# PowerWall_2020-05-24_01-53-03.net
KiCad netlist of a schematic drawn in EasyEDA
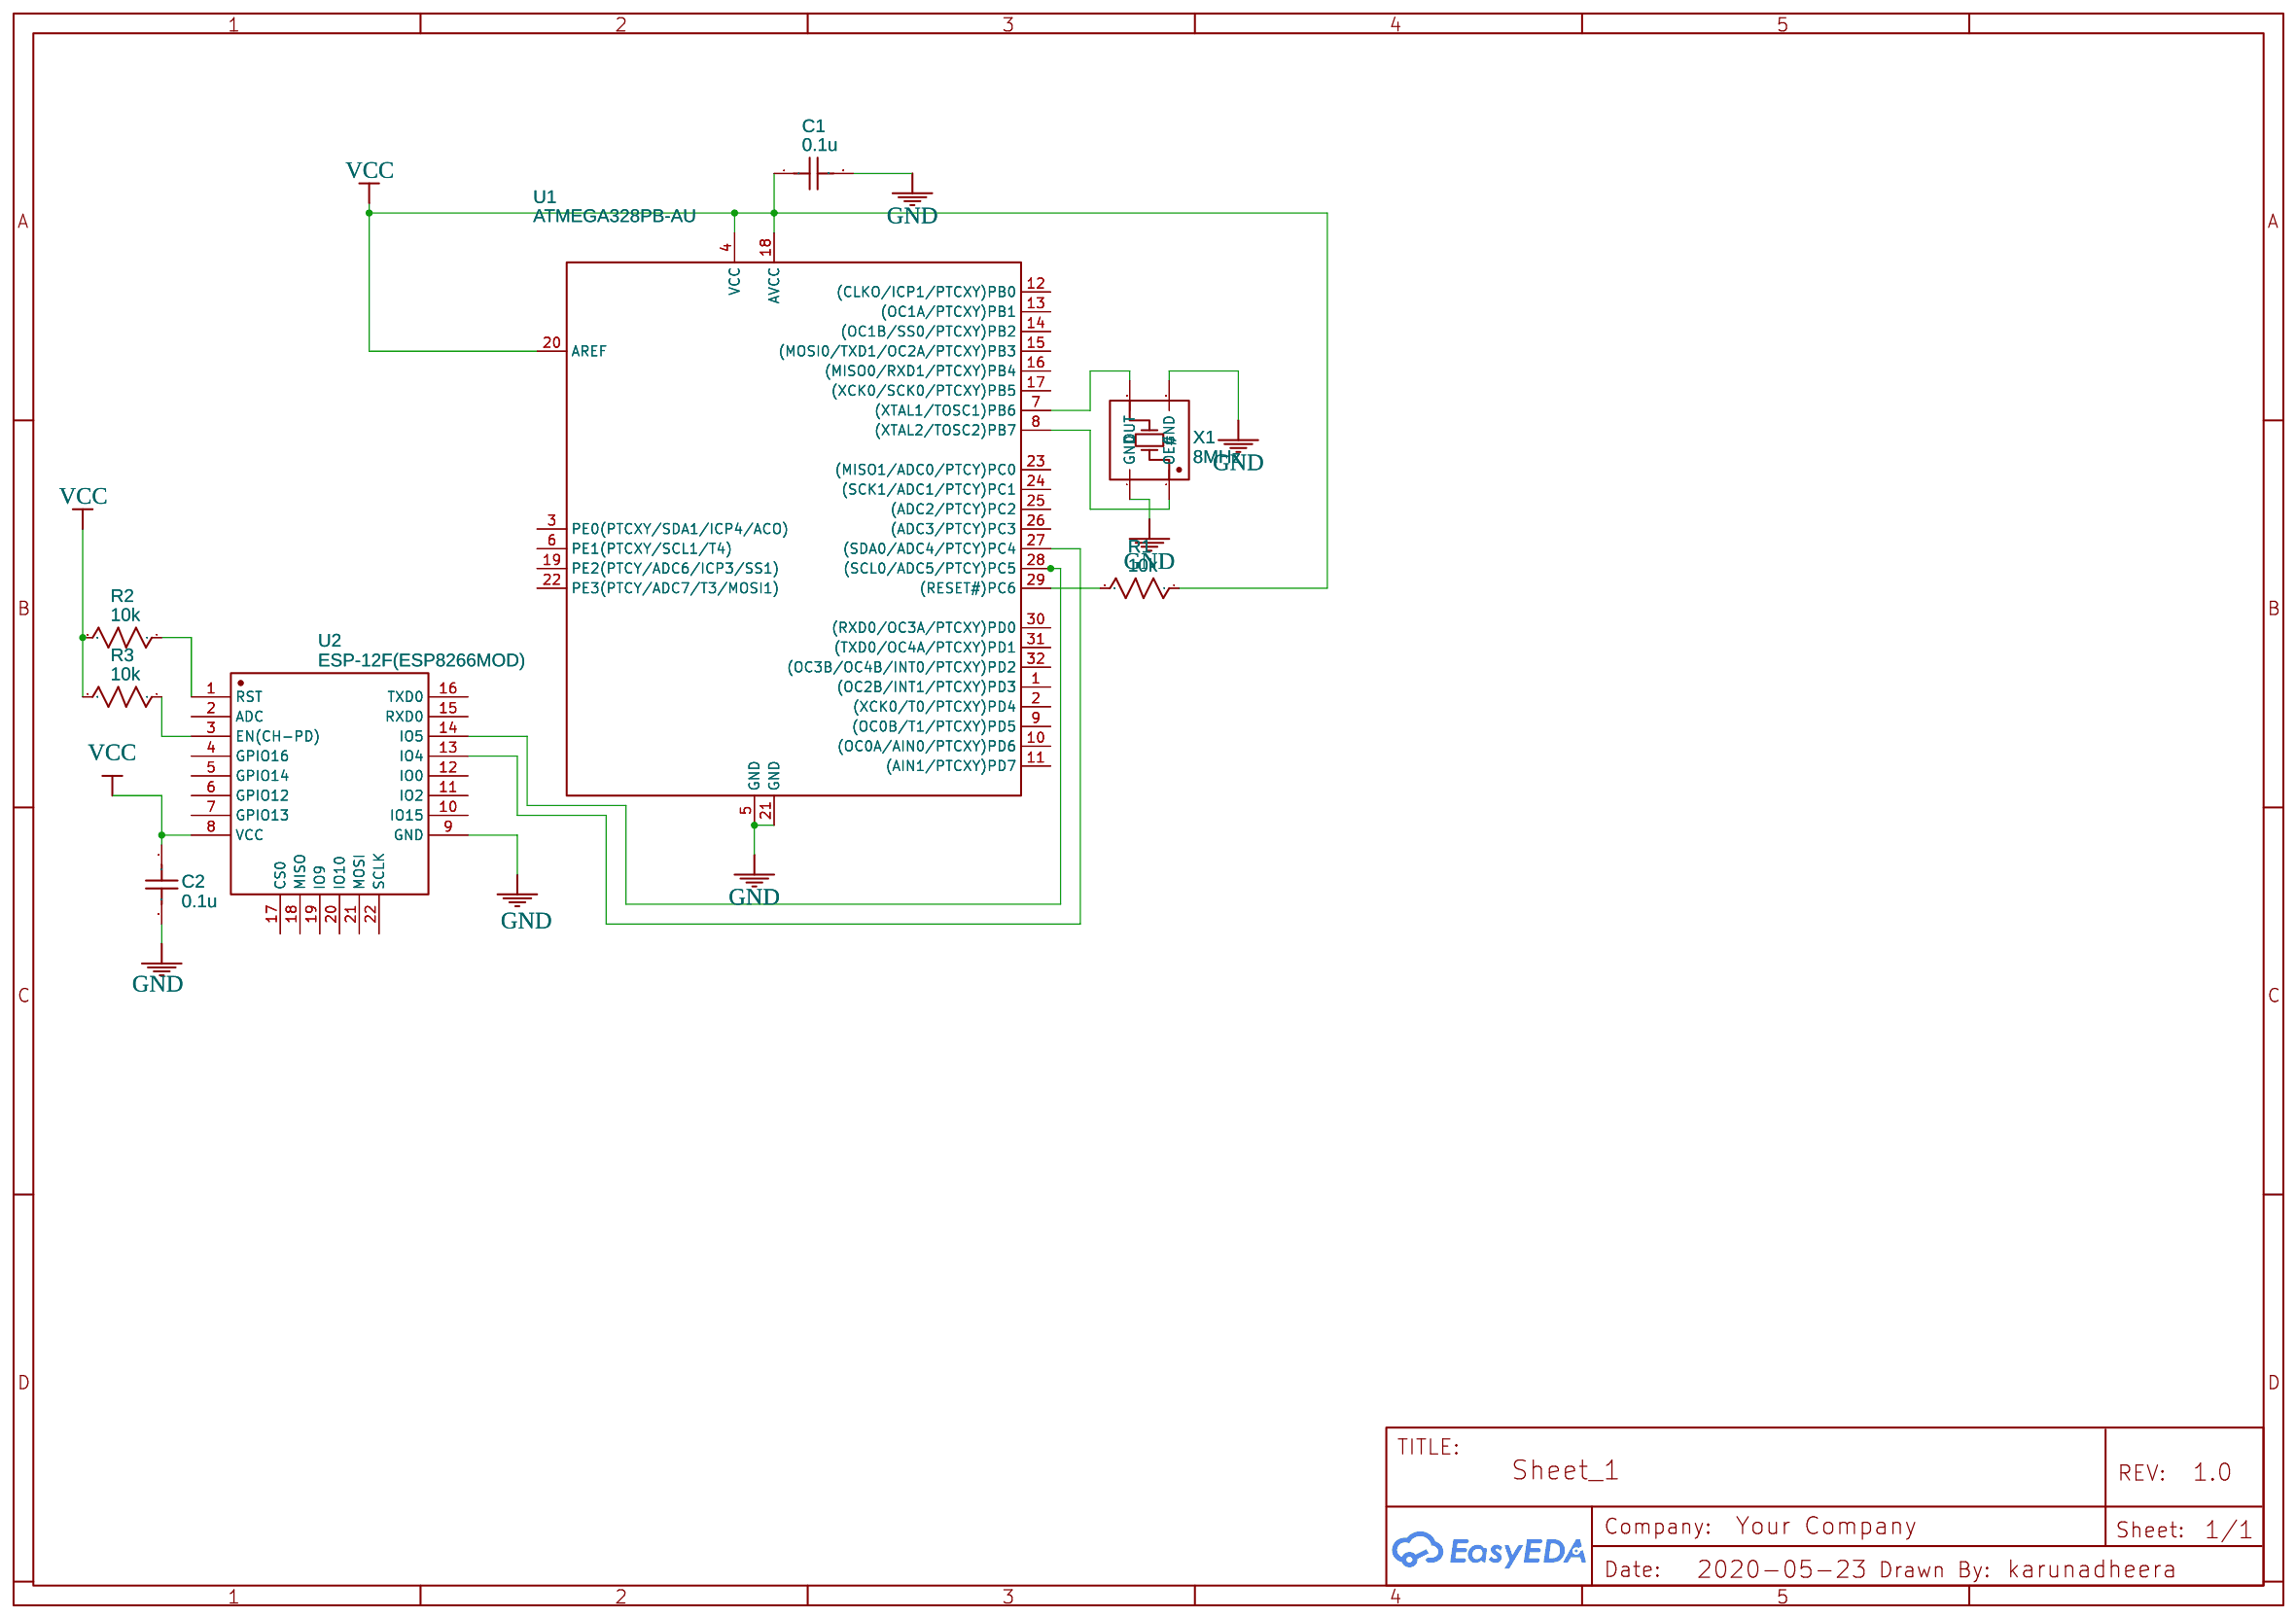
[diagram p0: schematic sheet]

(export (version "E")
  (design (tool "Eeschema 10.0.6"))
  (components
    (comp (ref "C1") (value "0.1u") (libsource (lib "") (part "C_0603_US")))
    (comp (ref "C2") (value "0.1u") (libsource (lib "") (part "C_0603_US_1")))
    (comp (ref "R1")
      (value "10k")
      (fields
        (field (name "BOM_Manufacturer Part") "NCP15XW222J03RC")
        (field (name "BOM_Supplier Part") "C98100")
      )
      (libsource (lib "") (part "R_0201_US"))
    )
    (comp (ref "R2")
      (value "10k")
      (fields
        (field (name "BOM_Manufacturer Part") "NCP15XW222J03RC")
        (field (name "BOM_Supplier Part") "C98100")
      )
      (libsource (lib "") (part "R_0201_US"))
    )
    (comp (ref "R3")
      (value "10k")
      (fields
        (field (name "BOM_Manufacturer Part") "NCP15XW222J03RC")
        (field (name "BOM_Supplier Part") "C98100")
      )
      (libsource (lib "") (part "R_0201_US"))
    )
    (comp (ref "U1")
      (value "ATMEGA328PB-AU")
      (fields (field (name "BOM_Supplier Part") "C132230"))
      (libsource (lib "") (part "ATMEGA328PB-AU"))
    )
    (comp (ref "U2")
      (value "ESP-12F(ESP8266MOD)")
      (fields (field (name "BOM_Supplier Part") "C82891"))
      (libsource (lib "") (part "ESP-12F(ESP8266MOD)"))
    )
    (comp (ref "X1")
      (value "8MHz")
      (fields
        (field (name "BOM_Manufacturer Part") "XXDCELNANF-8MHZ")
        (field (name "BOM_Supplier Part") "C367183")
      )
      (libsource (lib "") (part "XXDCELNANF-8MHZ"))
    )
  )
  (nets
    (net (code "1") (name "GND") (class "Default")
      (node (ref "C1") (pin "2") (pinfunction "2_2") (pintype "unspecified"))
      (node (ref "C2") (pin "2") (pinfunction "2_2") (pintype "unspecified"))
      (node (ref "U1") (pin "21") (pinfunction "GND_21") (pintype "bidirectional"))
      (node (ref "U1") (pin "5") (pinfunction "GND_5") (pintype "bidirectional"))
      (node (ref "U2") (pin "9") (pinfunction "GND_9") (pintype "unspecified"))
      (node (ref "X1") (pin "2") (pinfunction "GND_2") (pintype "input"))
      (node (ref "X1") (pin "4") (pinfunction "GND_4") (pintype "input"))
    )
    (net (code "2") (name "Net-(U1-(RESET#)PC6)") (class "Default")
      (node (ref "R1") (pin "2") (pinfunction "2_2") (pintype "unspecified"))
      (node (ref "U1") (pin "29") (pinfunction "(RESET#)PC6_29") (pintype "bidirectional"))
    )
    (net (code "3") (name "Net-(U1-(SCL0{slash}ADC5{slash}PTCY)PC5)") (class "Default")
      (node (ref "U1") (pin "28") (pinfunction "(SCL0/ADC5/PTCY)PC5_28") (pintype "bidirectional"))
      (node (ref "U2") (pin "14") (pinfunction "IO5_14") (pintype "unspecified"))
    )
    (net (code "4") (name "Net-(U1-(SDA0{slash}ADC4{slash}PTCY)PC4)") (class "Default")
      (node (ref "U1") (pin "27") (pinfunction "(SDA0/ADC4/PTCY)PC4_27") (pintype "bidirectional"))
      (node (ref "U2") (pin "13") (pinfunction "IO4_13") (pintype "unspecified"))
    )
    (net (code "5") (name "Net-(U1-(XTAL1{slash}TOSC1)PB6)") (class "Default")
      (node (ref "U1") (pin "7") (pinfunction "(XTAL1/TOSC1)PB6_7") (pintype "bidirectional"))
      (node (ref "X1") (pin "3") (pinfunction "OUT_3") (pintype "input"))
    )
    (net (code "6") (name "Net-(U1-(XTAL2{slash}TOSC2)PB7)") (class "Default")
      (node (ref "U1") (pin "8") (pinfunction "(XTAL2/TOSC2)PB7_8") (pintype "bidirectional"))
      (node (ref "X1") (pin "1") (pinfunction "OE#_1") (pintype "input"))
    )
    (net (code "7") (name "Net-(U2-EN(CH-PD))") (class "Default")
      (node (ref "R3") (pin "1") (pinfunction "1_1") (pintype "unspecified"))
      (node (ref "U2") (pin "3") (pinfunction "EN(CH-PD)_3") (pintype "unspecified"))
    )
    (net (code "8") (name "Net-(U2-RST)") (class "Default")
      (node (ref "R2") (pin "1") (pinfunction "1_1") (pintype "unspecified"))
      (node (ref "U2") (pin "1") (pinfunction "RST_1") (pintype "unspecified"))
    )
    (net (code "9") (name "VCC") (class "Default")
      (node (ref "C1") (pin "1") (pinfunction "1_1") (pintype "unspecified"))
      (node (ref "C2") (pin "1") (pinfunction "1_1") (pintype "unspecified"))
      (node (ref "R1") (pin "1") (pinfunction "1_1") (pintype "unspecified"))
      (node (ref "R2") (pin "2") (pinfunction "2_2") (pintype "unspecified"))
      (node (ref "R3") (pin "2") (pinfunction "2_2") (pintype "unspecified"))
      (node (ref "U1") (pin "18") (pinfunction "AVCC_18") (pintype "bidirectional"))
      (node (ref "U1") (pin "20") (pinfunction "AREF_20") (pintype "bidirectional"))
      (node (ref "U1") (pin "4") (pinfunction "VCC_4") (pintype "bidirectional"))
      (node (ref "U2") (pin "8") (pinfunction "VCC_8") (pintype "unspecified"))
    )
    (net (code "10") (name "unconnected-(U1-(ADC2{slash}PTCY)PC2-Pad25)") (class "Default")
      (node (ref "U1") (pin "25") (pinfunction "(ADC2/PTCY)PC2_25") (pintype "bidirectional"))
    )
    (net (code "11") (name "unconnected-(U1-(ADC3{slash}PTCY)PC3-Pad26)") (class "Default")
      (node (ref "U1") (pin "26") (pinfunction "(ADC3/PTCY)PC3_26") (pintype "bidirectional"))
    )
    (net (code "12") (name "unconnected-(U1-(AIN1{slash}PTCXY)PD7-Pad11)") (class "Default")
      (node (ref "U1") (pin "11") (pinfunction "(AIN1/PTCXY)PD7_11") (pintype "bidirectional"))
    )
    (net (code "13") (name "unconnected-(U1-(CLKO{slash}ICP1{slash}PTCXY)PB0-Pad12)") (class "Default")
      (node (ref "U1") (pin "12") (pinfunction "(CLKO/ICP1/PTCXY)PB0_12") (pintype "bidirectional"))
    )
    (net (code "14") (name "unconnected-(U1-(MISO0{slash}RXD1{slash}PTCXY)PB4-Pad16)") (class "Default")
      (node (ref "U1") (pin "16") (pinfunction "(MISO0/RXD1/PTCXY)PB4_16") (pintype "bidirectional"))
    )
    (net (code "15") (name "unconnected-(U1-(MISO1{slash}ADC0{slash}PTCY)PC0-Pad23)") (class "Default")
      (node (ref "U1") (pin "23") (pinfunction "(MISO1/ADC0/PTCY)PC0_23") (pintype "bidirectional"))
    )
    (net (code "16") (name "unconnected-(U1-(MOSI0{slash}TXD1{slash}OC2A{slash}PTCXY)PB3-Pad15)") (class "Default")
      (node (ref "U1") (pin "15") (pinfunction "(MOSI0/TXD1/OC2A/PTCXY)PB3_15") (pintype "bidirectional"))
    )
    (net (code "17") (name "unconnected-(U1-(OC0A{slash}AIN0{slash}PTCXY)PD6-Pad10)") (class "Default")
      (node (ref "U1") (pin "10") (pinfunction "(OC0A/AIN0/PTCXY)PD6_10") (pintype "bidirectional"))
    )
    (net (code "18") (name "unconnected-(U1-(OC0B{slash}T1{slash}PTCXY)PD5-Pad9)") (class "Default")
      (node (ref "U1") (pin "9") (pinfunction "(OC0B/T1/PTCXY)PD5_9") (pintype "bidirectional"))
    )
    (net (code "19") (name "unconnected-(U1-(OC1A{slash}PTCXY)PB1-Pad13)") (class "Default")
      (node (ref "U1") (pin "13") (pinfunction "(OC1A/PTCXY)PB1_13") (pintype "bidirectional"))
    )
    (net (code "20") (name "unconnected-(U1-(OC1B{slash}SS0{slash}PTCXY)PB2-Pad14)") (class "Default")
      (node (ref "U1") (pin "14") (pinfunction "(OC1B/SS0/PTCXY)PB2_14") (pintype "bidirectional"))
    )
    (net (code "21") (name "unconnected-(U1-(OC2B{slash}INT1{slash}PTCXY)PD3-Pad1)") (class "Default")
      (node (ref "U1") (pin "1") (pinfunction "(OC2B/INT1/PTCXY)PD3_1") (pintype "bidirectional"))
    )
    (net (code "22") (name "unconnected-(U1-(OC3B{slash}OC4B{slash}INT0{slash}PTCXY)PD2-Pad32)") (class "Default")
      (node (ref "U1") (pin "32") (pinfunction "(OC3B/OC4B/INT0/PTCXY)PD2_32") (pintype "bidirectional"))
    )
    (net (code "23") (name "unconnected-(U1-(RXD0{slash}OC3A{slash}PTCXY)PD0-Pad30)") (class "Default")
      (node (ref "U1") (pin "30") (pinfunction "(RXD0/OC3A/PTCXY)PD0_30") (pintype "bidirectional"))
    )
    (net (code "24") (name "unconnected-(U1-(SCK1{slash}ADC1{slash}PTCY)PC1-Pad24)") (class "Default")
      (node (ref "U1") (pin "24") (pinfunction "(SCK1/ADC1/PTCY)PC1_24") (pintype "bidirectional"))
    )
    (net (code "25") (name "unconnected-(U1-(TXD0{slash}OC4A{slash}PTCXY)PD1-Pad31)") (class "Default")
      (node (ref "U1") (pin "31") (pinfunction "(TXD0/OC4A/PTCXY)PD1_31") (pintype "bidirectional"))
    )
    (net (code "26") (name "unconnected-(U1-(XCK0{slash}SCK0{slash}PTCXY)PB5-Pad17)") (class "Default")
      (node (ref "U1") (pin "17") (pinfunction "(XCK0/SCK0/PTCXY)PB5_17") (pintype "bidirectional"))
    )
    (net (code "27") (name "unconnected-(U1-(XCK0{slash}T0{slash}PTCXY)PD4-Pad2)") (class "Default")
      (node (ref "U1") (pin "2") (pinfunction "(XCK0/T0/PTCXY)PD4_2") (pintype "bidirectional"))
    )
    (net (code "28") (name "unconnected-(U1-PE0(PTCXY{slash}SDA1{slash}ICP4{slash}ACO)-Pad3)") (class "Default")
      (node (ref "U1") (pin "3") (pinfunction "PE0(PTCXY/SDA1/ICP4/ACO)_3") (pintype "bidirectional"))
    )
    (net (code "29") (name "unconnected-(U1-PE1(PTCXY{slash}SCL1{slash}T4)-Pad6)") (class "Default")
      (node (ref "U1") (pin "6") (pinfunction "PE1(PTCXY/SCL1/T4)_6") (pintype "bidirectional"))
    )
    (net (code "30") (name "unconnected-(U1-PE2(PTCY{slash}ADC6{slash}ICP3{slash}SS1)-Pad19)") (class "Default")
      (node (ref "U1") (pin "19") (pinfunction "PE2(PTCY/ADC6/ICP3/SS1)_19") (pintype "bidirectional"))
    )
    (net (code "31") (name "unconnected-(U1-PE3(PTCY{slash}ADC7{slash}T3{slash}MOSI1)-Pad22)") (class "Default")
      (node (ref "U1") (pin "22") (pinfunction "PE3(PTCY/ADC7/T3/MOSI1)_22") (pintype "bidirectional"))
    )
    (net (code "32") (name "unconnected-(U2-ADC-Pad2)") (class "Default")
      (node (ref "U2") (pin "2") (pinfunction "ADC_2") (pintype "unspecified"))
    )
    (net (code "33") (name "unconnected-(U2-CS0-Pad17)") (class "Default")
      (node (ref "U2") (pin "17") (pinfunction "CS0_17") (pintype "unspecified"))
    )
    (net (code "34") (name "unconnected-(U2-GPIO12-Pad6)") (class "Default")
      (node (ref "U2") (pin "6") (pinfunction "GPIO12_6") (pintype "unspecified"))
    )
    (net (code "35") (name "unconnected-(U2-GPIO13-Pad7)") (class "Default")
      (node (ref "U2") (pin "7") (pinfunction "GPIO13_7") (pintype "unspecified"))
    )
    (net (code "36") (name "unconnected-(U2-GPIO14-Pad5)") (class "Default")
      (node (ref "U2") (pin "5") (pinfunction "GPIO14_5") (pintype "unspecified"))
    )
    (net (code "37") (name "unconnected-(U2-GPIO16-Pad4)") (class "Default")
      (node (ref "U2") (pin "4") (pinfunction "GPIO16_4") (pintype "unspecified"))
    )
    (net (code "38") (name "unconnected-(U2-IO0-Pad12)") (class "Default")
      (node (ref "U2") (pin "12") (pinfunction "IO0_12") (pintype "unspecified"))
    )
    (net (code "39") (name "unconnected-(U2-IO2-Pad11)") (class "Default")
      (node (ref "U2") (pin "11") (pinfunction "IO2_11") (pintype "unspecified"))
    )
    (net (code "40") (name "unconnected-(U2-IO9-Pad19)") (class "Default")
      (node (ref "U2") (pin "19") (pinfunction "IO9_19") (pintype "unspecified"))
    )
    (net (code "41") (name "unconnected-(U2-IO10-Pad20)") (class "Default")
      (node (ref "U2") (pin "20") (pinfunction "IO10_20") (pintype "unspecified"))
    )
    (net (code "42") (name "unconnected-(U2-IO15-Pad10)") (class "Default")
      (node (ref "U2") (pin "10") (pinfunction "IO15_10") (pintype "unspecified"))
    )
    (net (code "43") (name "unconnected-(U2-MISO-Pad18)") (class "Default")
      (node (ref "U2") (pin "18") (pinfunction "MISO_18") (pintype "unspecified"))
    )
    (net (code "44") (name "unconnected-(U2-MOSI-Pad21)") (class "Default")
      (node (ref "U2") (pin "21") (pinfunction "MOSI_21") (pintype "unspecified"))
    )
    (net (code "45") (name "unconnected-(U2-RXD0-Pad15)") (class "Default")
      (node (ref "U2") (pin "15") (pinfunction "RXD0_15") (pintype "unspecified"))
    )
    (net (code "46") (name "unconnected-(U2-SCLK-Pad22)") (class "Default")
      (node (ref "U2") (pin "22") (pinfunction "SCLK_22") (pintype "unspecified"))
    )
    (net (code "47") (name "unconnected-(U2-TXD0-Pad16)") (class "Default")
      (node (ref "U2") (pin "16") (pinfunction "TXD0_16") (pintype "unspecified"))
    )
  )
)
